# SmartThermo1_6.net
KiCad netlist of a schematic drawn in EAGLE
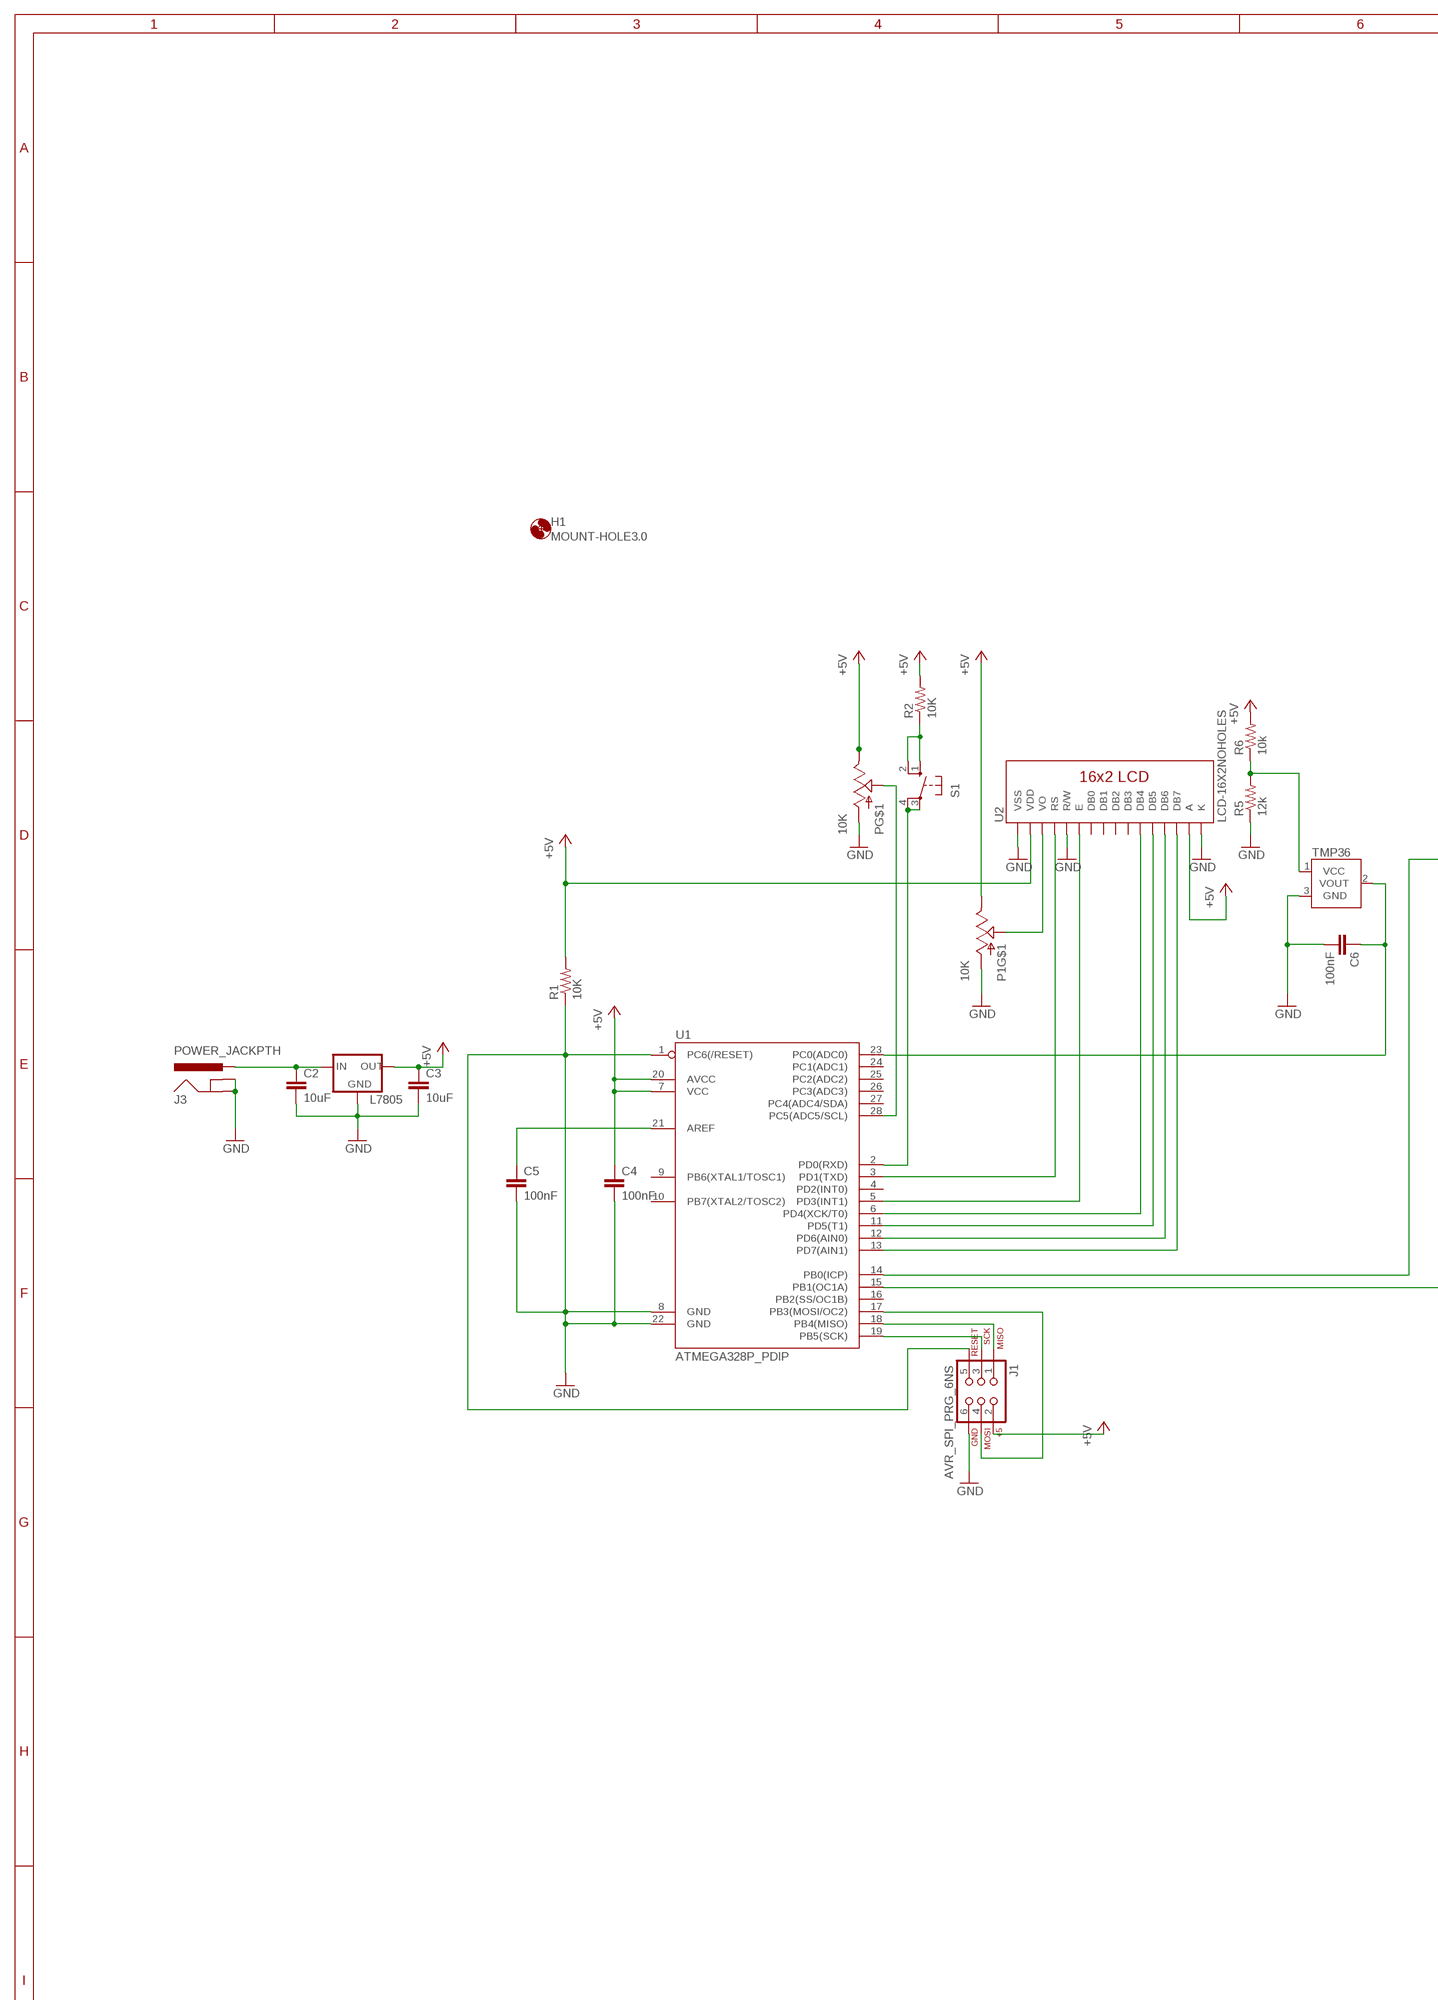
[diagram p0: schematic, sheet 1, part 1 of 2]
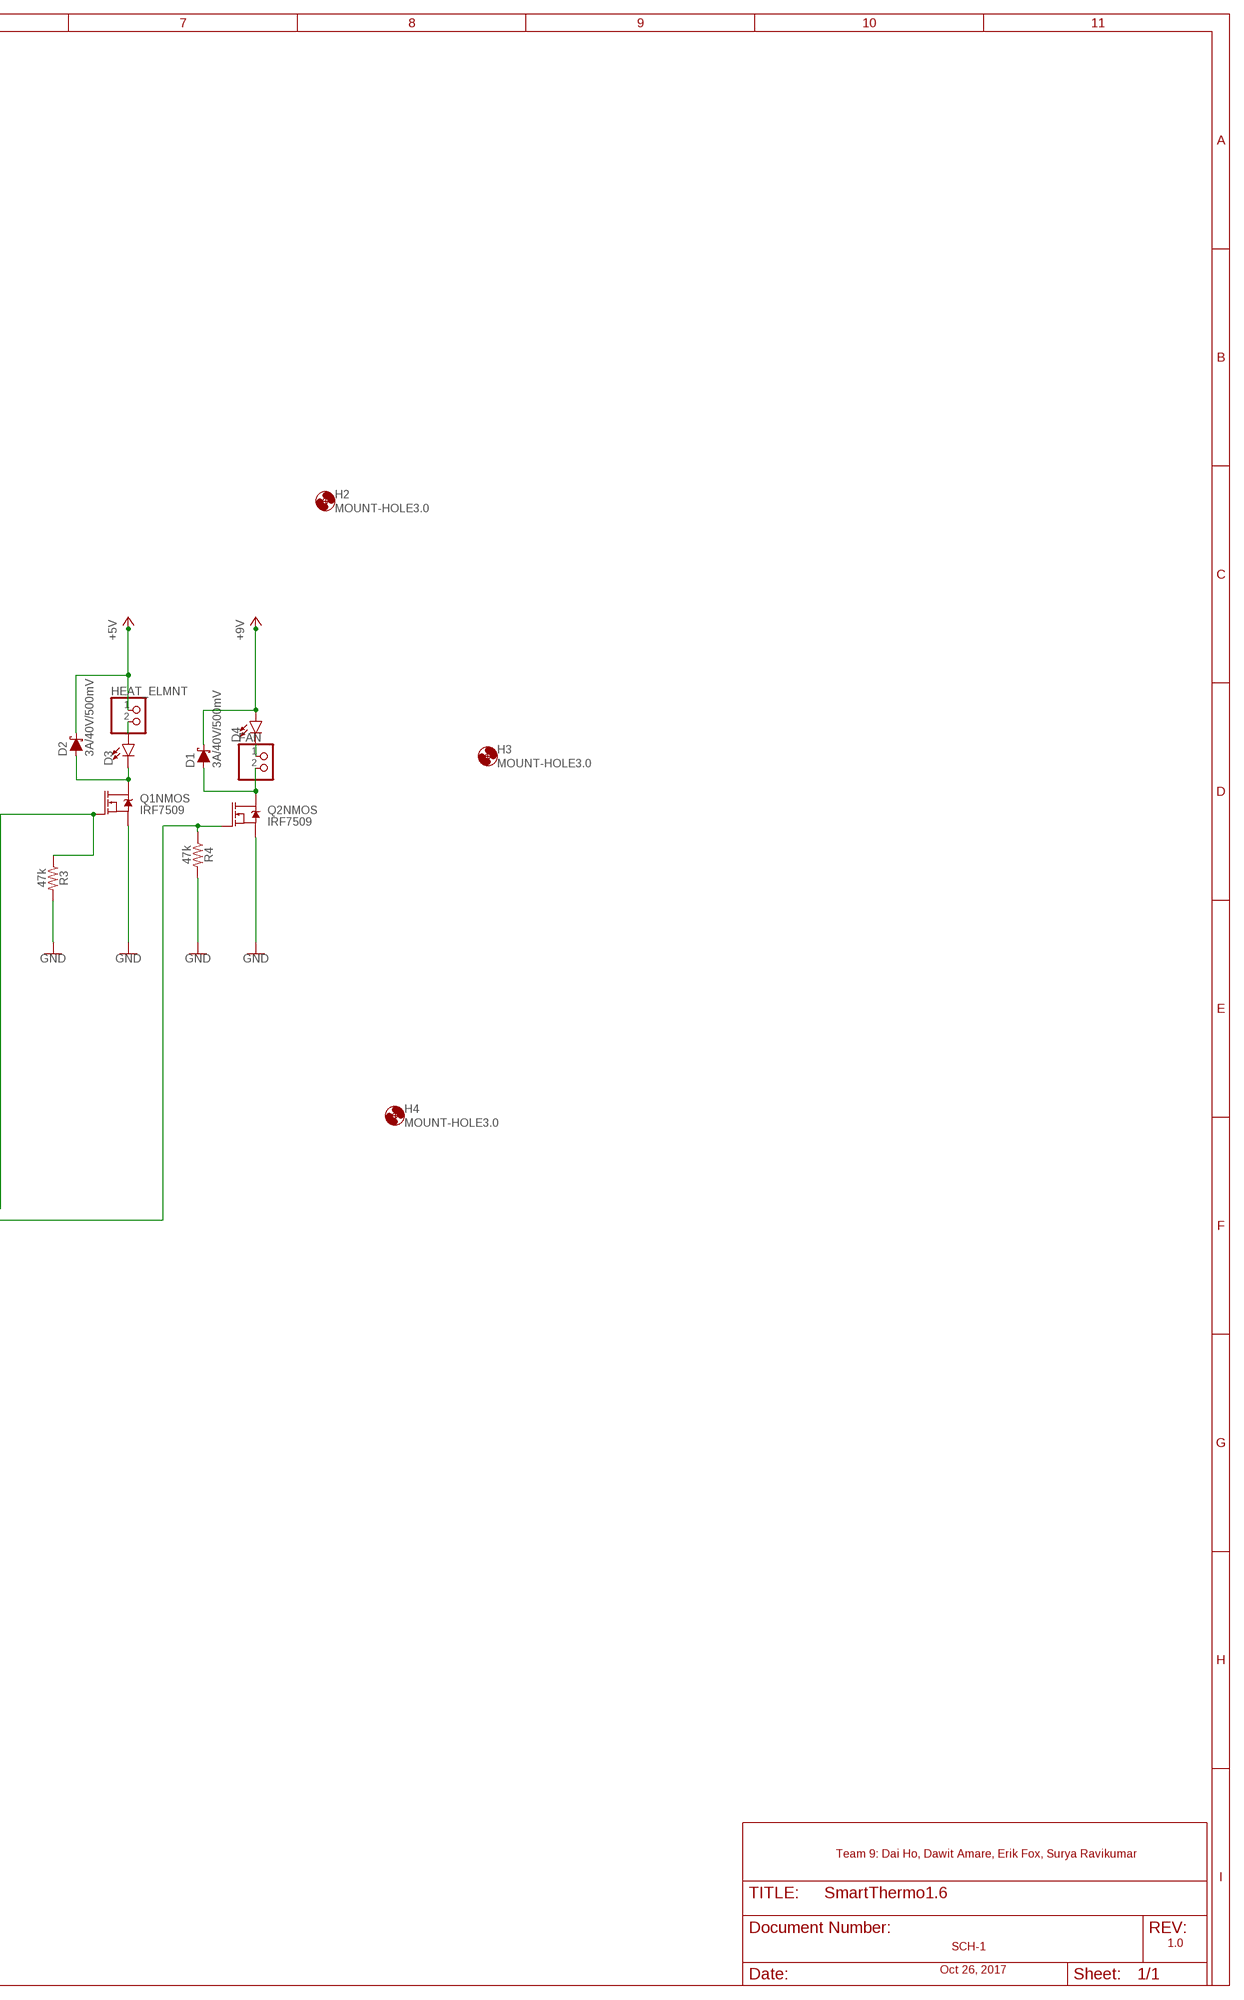
[diagram p1: schematic, sheet 1, part 2 of 2]

(export (version "E")
  (design (tool "Eeschema 10.0.6"))
  (components
    (comp (ref "C2")
      (value "10uF")
      (footprint "eagle-import:C7.5B3")
      (libsource (lib "eagle-import") (part "C7.5/3"))
    )
    (comp (ref "C3")
      (value "10uF")
      (footprint "eagle-import:C7.5B3")
      (libsource (lib "eagle-import") (part "C7.5/3"))
    )
    (comp (ref "C4")
      (value "100nF")
      (footprint "eagle-import:C2.5-2")
      (libsource (lib "eagle-import") (part "C2.5/2"))
    )
    (comp (ref "C5")
      (value "100nF")
      (footprint "eagle-import:C2.5-2")
      (libsource (lib "eagle-import") (part "C2.5/2"))
    )
    (comp (ref "C6")
      (value "100nF")
      (footprint "eagle-import:C2.5-2")
      (libsource (lib "eagle-import") (part "C2.5/2"))
    )
    (comp (ref "D1")
      (value "3A/40V/500mV")
      (footprint "eagle-import:SMA-DIODE")
      (libsource (lib "eagle-import") (part "DIODE-SCHOTTKY-B340A"))
    )
    (comp (ref "D2")
      (value "3A/40V/500mV")
      (footprint "eagle-import:SMA-DIODE")
      (libsource (lib "eagle-import") (part "DIODE-SCHOTTKY-B340A"))
    )
    (comp (ref "D3")
      (value "LED3MM")
      (footprint "eagle-import:LED_3MM")
      (libsource (lib "eagle-import") (part "LED3MM"))
    )
    (comp (ref "D4")
      (value "LED3MM")
      (footprint "eagle-import:LED_3MM")
      (libsource (lib "eagle-import") (part "LED3MM"))
    )
    (comp (ref "FAN")
      (value "PINHD-1X2/90")
      (footprint "eagle-import:1X02_90")
      (libsource (lib "eagle-import") (part "PINHD-1X2/90"))
    )
    (comp (ref "H1")
      (value "MOUNT-HOLE3.0")
      (footprint "eagle-import:3,0")
      (libsource (lib "eagle-import") (part "MOUNT-HOLE3.0"))
    )
    (comp (ref "H2")
      (value "MOUNT-HOLE3.0")
      (footprint "eagle-import:3,0")
      (libsource (lib "eagle-import") (part "MOUNT-HOLE3.0"))
    )
    (comp (ref "H3")
      (value "MOUNT-HOLE3.0")
      (footprint "eagle-import:3,0")
      (libsource (lib "eagle-import") (part "MOUNT-HOLE3.0"))
    )
    (comp (ref "H4")
      (value "MOUNT-HOLE3.0")
      (footprint "eagle-import:3,0")
      (libsource (lib "eagle-import") (part "MOUNT-HOLE3.0"))
    )
    (comp (ref "HEAT_ELMNT")
      (value "PINHD-1X2/90")
      (footprint "eagle-import:1X02_90")
      (libsource (lib "eagle-import") (part "PINHD-1X2/90"))
    )
    (comp (ref "J1")
      (value "AVR_SPI_PRG_6NS")
      (footprint "eagle-import:2X3-NS")
      (libsource (lib "eagle-import") (part "AVR_SPI_PRG_6NS"))
    )
    (comp (ref "J3")
      (value "POWER_JACKPTH")
      (footprint "eagle-import:POWER_JACK_PTH")
      (libsource (lib "eagle-import") (part "POWER_JACKPTH"))
    )
    (comp (ref "L7805")
      (value "78XXL")
      (footprint "eagle-import:78XXL")
      (libsource (lib "eagle-import") (part "78XXL"))
    )
    (comp (ref "P")
      (value "10K")
      (footprint "eagle-import:POT_PTH")
      (libsource (lib "eagle-import") (part "POT_SWITCHPOT_PTH"))
    )
    (comp (ref "P1")
      (value "10K")
      (footprint "eagle-import:POT_PTH")
      (libsource (lib "eagle-import") (part "POT_SWITCHPOT_PTH"))
    )
    (comp (ref "Q1")
      (value "IRF7509")
      (footprint "eagle-import:MSOP8")
      (libsource (lib "eagle-import") (part "IRF7509"))
    )
    (comp (ref "Q2")
      (value "IRF7509")
      (footprint "eagle-import:MSOP8")
      (libsource (lib "eagle-import") (part "IRF7509"))
    )
    (comp (ref "R1")
      (value "10K")
      (footprint "eagle-import:1206")
      (libsource (lib "eagle-import") (part "RESISTOR1206"))
    )
    (comp (ref "R2")
      (value "10K")
      (footprint "eagle-import:1206")
      (libsource (lib "eagle-import") (part "RESISTOR1206"))
    )
    (comp (ref "R3")
      (value "47k")
      (footprint "eagle-import:0603")
      (libsource (lib "eagle-import") (part "47KOHM-0603-1/10W-1%"))
    )
    (comp (ref "R4")
      (value "47k")
      (footprint "eagle-import:0603")
      (libsource (lib "eagle-import") (part "47KOHM-0603-1/10W-1%"))
    )
    (comp (ref "R5")
      (value "12k")
      (footprint "eagle-import:0204_5")
      (libsource (lib "eagle-import") (part "R-US_0204/5"))
    )
    (comp (ref "R6")
      (value "10k")
      (footprint "eagle-import:0204_5")
      (libsource (lib "eagle-import") (part "R-US_0204/5"))
    )
    (comp (ref "S1")
      (value "10-XX")
      (footprint "eagle-import:B3F-10XX")
      (fields (field (name "MPN") "B3F-1000"))
      (libsource (lib "eagle-import") (part "10-XX"))
    )
    (comp (ref "TMP36")
      (value "TMP36GT9")
      (footprint "eagle-import:TO-92")
      (libsource (lib "eagle-import") (part "TMP36GT9"))
    )
    (comp (ref "U1")
      (value "ATMEGA328P_PDIP")
      (footprint "eagle-import:DIL28-3")
      (libsource (lib "eagle-import") (part "ATMEGA328P_PDIP"))
    )
    (comp (ref "U2")
      (value "LCD-16X2NOHOLES")
      (footprint "eagle-import:LCD-16X2_NOHOLES")
      (libsource (lib "eagle-import") (part "LCD-16X2NOHOLES"))
    )
  )
  (nets
    (net (code "1") (name "+5V") (class "Default")
      (node (ref "C3") (pin "1") (pinfunction "1_1") (pintype "passive"))
      (node (ref "C4") (pin "1") (pinfunction "1_1") (pintype "passive"))
      (node (ref "D1") (pin "C") (pinfunction "C_C") (pintype "passive"))
      (node (ref "D2") (pin "C") (pinfunction "C_C") (pintype "passive"))
      (node (ref "D4") (pin "A") (pinfunction "A_A") (pintype "passive"))
      (node (ref "HEAT_ELMNT") (pin "1") (pinfunction "1_1") (pintype "passive"))
      (node (ref "J1") (pin "2") (pinfunction "2_2") (pintype "passive"))
      (node (ref "L7805") (pin "OUT") (pinfunction "OUT_OUT") (pintype "passive"))
      (node (ref "P") (pin "E@2") (pinfunction "E_E@2") (pintype "passive"))
      (node (ref "P1") (pin "E@2") (pinfunction "E_E@2") (pintype "passive"))
      (node (ref "R1") (pin "2") (pinfunction "2_2") (pintype "passive"))
      (node (ref "R2") (pin "2") (pinfunction "2_2") (pintype "passive"))
      (node (ref "R6") (pin "2") (pinfunction "2_2") (pintype "passive"))
      (node (ref "U1") (pin "20") (pinfunction "AVCC_20") (pintype "bidirectional"))
      (node (ref "U1") (pin "7") (pinfunction "VCC_7") (pintype "bidirectional"))
      (node (ref "U2") (pin "15") (pinfunction "A_15") (pintype "power_in"))
      (node (ref "U2") (pin "2") (pinfunction "VDD_2") (pintype "power_in"))
    )
    (net (code "2") (name "GND") (class "Default")
      (node (ref "C2") (pin "2") (pinfunction "2_2") (pintype "passive"))
      (node (ref "C3") (pin "2") (pinfunction "2_2") (pintype "passive"))
      (node (ref "C4") (pin "2") (pinfunction "2_2") (pintype "passive"))
      (node (ref "C5") (pin "2") (pinfunction "2_2") (pintype "passive"))
      (node (ref "C6") (pin "2") (pinfunction "2_2") (pintype "passive"))
      (node (ref "J1") (pin "5") (pinfunction "5_5") (pintype "passive"))
      (node (ref "J1") (pin "6") (pinfunction "6_6") (pintype "passive"))
      (node (ref "J3") (pin "GND") (pinfunction "GND_GND") (pintype "bidirectional"))
      (node (ref "J3") (pin "GNDBREAK") (pinfunction "GNDBREAK_GNDBREAK") (pintype "bidirectional"))
      (node (ref "L7805") (pin "GND") (pinfunction "GND_GND") (pintype "input"))
      (node (ref "P") (pin "E@1") (pinfunction "A_E@1") (pintype "passive"))
      (node (ref "P1") (pin "E@1") (pinfunction "A_E@1") (pintype "passive"))
      (node (ref "Q1") (pin "1") (pinfunction "S_1") (pintype "bidirectional"))
      (node (ref "Q2") (pin "1") (pinfunction "S_1") (pintype "bidirectional"))
      (node (ref "R1") (pin "1") (pinfunction "1_1") (pintype "passive"))
      (node (ref "R3") (pin "2") (pinfunction "2_2") (pintype "passive"))
      (node (ref "R4") (pin "2") (pinfunction "2_2") (pintype "passive"))
      (node (ref "R5") (pin "1") (pinfunction "1_1") (pintype "passive"))
      (node (ref "TMP36") (pin "3") (pinfunction "GND_3") (pintype "bidirectional"))
      (node (ref "U1") (pin "1") (pinfunction "PC6(/RESET)_1") (pintype "bidirectional"))
      (node (ref "U1") (pin "22") (pinfunction "GND_22") (pintype "bidirectional"))
      (node (ref "U1") (pin "8") (pinfunction "GND_8") (pintype "bidirectional"))
      (node (ref "U2") (pin "1") (pinfunction "VSS_1") (pintype "power_in"))
      (node (ref "U2") (pin "16") (pinfunction "K_16") (pintype "power_in"))
      (node (ref "U2") (pin "5") (pinfunction "R/W_5") (pintype "input"))
    )
    (net (code "3") (name "Net-(C2-Pad1)") (class "Default")
      (node (ref "C2") (pin "1") (pinfunction "1_1") (pintype "passive"))
      (node (ref "J3") (pin "PWR") (pinfunction "PWR_PWR") (pintype "bidirectional"))
      (node (ref "L7805") (pin "IN") (pinfunction "IN_IN") (pintype "input"))
    )
    (net (code "4") (name "Net-(D1-PadA)") (class "Default")
      (node (ref "D1") (pin "A") (pinfunction "A_A") (pintype "passive"))
      (node (ref "FAN") (pin "2") (pinfunction "2_2") (pintype "passive"))
      (node (ref "Q2") (pin "7") (pinfunction "D_7") (pintype "bidirectional"))
      (node (ref "Q2") (pin "8") (pinfunction "D_8") (pintype "bidirectional"))
    )
    (net (code "5") (name "Net-(D3-C)") (class "Default")
      (node (ref "D2") (pin "A") (pinfunction "A_A") (pintype "passive"))
      (node (ref "D3") (pin "K") (pinfunction "C_K") (pintype "passive"))
      (node (ref "Q1") (pin "7") (pinfunction "D_7") (pintype "bidirectional"))
      (node (ref "Q1") (pin "8") (pinfunction "D_8") (pintype "bidirectional"))
    )
    (net (code "6") (name "Net-(D3-PadA)") (class "Default")
      (node (ref "D3") (pin "A") (pinfunction "A_A") (pintype "passive"))
      (node (ref "HEAT_ELMNT") (pin "2") (pinfunction "2_2") (pintype "passive"))
    )
    (net (code "7") (name "Net-(D4-C)") (class "Default")
      (node (ref "D4") (pin "K") (pinfunction "C_K") (pintype "passive"))
      (node (ref "FAN") (pin "1") (pinfunction "1_1") (pintype "passive"))
    )
    (net (code "8") (name "Net-(P1A-S)") (class "Default")
      (node (ref "P1") (pin "WAND") (pinfunction "S_WAND") (pintype "passive"))
      (node (ref "U2") (pin "3") (pinfunction "VO_3") (pintype "bidirectional"))
    )
    (net (code "9") (name "Net-(PA-S)") (class "Default")
      (node (ref "P") (pin "WAND") (pinfunction "S_WAND") (pintype "passive"))
      (node (ref "U1") (pin "28") (pinfunction "PC5(ADC5/SCL)_28") (pintype "bidirectional"))
    )
    (net (code "10") (name "Net-(Q1A-G)") (class "Default")
      (node (ref "Q1") (pin "2") (pinfunction "G_2") (pintype "bidirectional"))
      (node (ref "R3") (pin "1") (pinfunction "1_1") (pintype "passive"))
      (node (ref "U1") (pin "14") (pinfunction "PB0(ICP)_14") (pintype "bidirectional"))
    )
    (net (code "11") (name "Net-(Q2A-G)") (class "Default")
      (node (ref "Q2") (pin "2") (pinfunction "G_2") (pintype "bidirectional"))
      (node (ref "R4") (pin "1") (pinfunction "1_1") (pintype "passive"))
      (node (ref "U1") (pin "15") (pinfunction "PB1(OC1A)_15") (pintype "bidirectional"))
    )
    (net (code "12") (name "Net-(S1-P)") (class "Default")
      (node (ref "S1") (pin "3") (pinfunction "P_3") (pintype "passive"))
      (node (ref "S1") (pin "4") (pinfunction "P1_4") (pintype "passive"))
      (node (ref "U1") (pin "2") (pinfunction "PD0(RXD)_2") (pintype "bidirectional"))
    )
    (net (code "13") (name "Net-(S1-S)") (class "Default")
      (node (ref "R2") (pin "1") (pinfunction "1_1") (pintype "passive"))
      (node (ref "S1") (pin "1") (pinfunction "S_1") (pintype "passive"))
      (node (ref "S1") (pin "2") (pinfunction "S1_2") (pintype "passive"))
    )
    (net (code "14") (name "Net-(TMP36-VCC)") (class "Default")
      (node (ref "R5") (pin "2") (pinfunction "2_2") (pintype "passive"))
      (node (ref "R6") (pin "1") (pinfunction "1_1") (pintype "passive"))
      (node (ref "TMP36") (pin "1") (pinfunction "VCC_1") (pintype "bidirectional"))
    )
    (net (code "15") (name "Net-(TMP36-VOUT)") (class "Default")
      (node (ref "C6") (pin "1") (pinfunction "1_1") (pintype "passive"))
      (node (ref "TMP36") (pin "2") (pinfunction "VOUT_2") (pintype "bidirectional"))
      (node (ref "U1") (pin "23") (pinfunction "PC0(ADC0)_23") (pintype "bidirectional"))
    )
    (net (code "16") (name "Net-(U1-AREF)") (class "Default")
      (node (ref "C5") (pin "1") (pinfunction "1_1") (pintype "passive"))
      (node (ref "U1") (pin "21") (pinfunction "AREF_21") (pintype "bidirectional"))
    )
    (net (code "17") (name "Net-(U1-PB3(MOSI{slash}OC2))") (class "Default")
      (node (ref "J1") (pin "4") (pinfunction "4_4") (pintype "passive"))
      (node (ref "U1") (pin "17") (pinfunction "PB3(MOSI/OC2)_17") (pintype "bidirectional"))
    )
    (net (code "18") (name "Net-(U1-PB4(MISO))") (class "Default")
      (node (ref "J1") (pin "1") (pinfunction "1_1") (pintype "passive"))
      (node (ref "U1") (pin "18") (pinfunction "PB4(MISO)_18") (pintype "bidirectional"))
    )
    (net (code "19") (name "Net-(U1-PB5(SCK))") (class "Default")
      (node (ref "J1") (pin "3") (pinfunction "3_3") (pintype "passive"))
      (node (ref "U1") (pin "19") (pinfunction "PB5(SCK)_19") (pintype "bidirectional"))
    )
    (net (code "20") (name "Net-(U1-PD1(TXD))") (class "Default")
      (node (ref "U1") (pin "3") (pinfunction "PD1(TXD)_3") (pintype "bidirectional"))
      (node (ref "U2") (pin "4") (pinfunction "RS_4") (pintype "input"))
    )
    (net (code "21") (name "Net-(U1-PD3(INT1))") (class "Default")
      (node (ref "U1") (pin "5") (pinfunction "PD3(INT1)_5") (pintype "bidirectional"))
      (node (ref "U2") (pin "6") (pinfunction "E_6") (pintype "input"))
    )
    (net (code "22") (name "Net-(U1-PD4(XCK{slash}T0))") (class "Default")
      (node (ref "U1") (pin "6") (pinfunction "PD4(XCK/T0)_6") (pintype "bidirectional"))
      (node (ref "U2") (pin "11") (pinfunction "DB4_11") (pintype "bidirectional"))
    )
    (net (code "23") (name "Net-(U1-PD5(T1))") (class "Default")
      (node (ref "U1") (pin "11") (pinfunction "PD5(T1)_11") (pintype "bidirectional"))
      (node (ref "U2") (pin "12") (pinfunction "DB5_12") (pintype "bidirectional"))
    )
    (net (code "24") (name "Net-(U1-PD6(AIN0))") (class "Default")
      (node (ref "U1") (pin "12") (pinfunction "PD6(AIN0)_12") (pintype "bidirectional"))
      (node (ref "U2") (pin "13") (pinfunction "DB6_13") (pintype "bidirectional"))
    )
    (net (code "25") (name "Net-(U1-PD7(AIN1))") (class "Default")
      (node (ref "U1") (pin "13") (pinfunction "PD7(AIN1)_13") (pintype "bidirectional"))
      (node (ref "U2") (pin "14") (pinfunction "DB7_14") (pintype "bidirectional"))
    )
    (net (code "26") (name "unconnected-(U1-PB2(SS{slash}OC1B)-Pad16)") (class "Default")
      (node (ref "U1") (pin "16") (pinfunction "PB2(SS/OC1B)_16") (pintype "bidirectional"))
    )
    (net (code "27") (name "unconnected-(U1-PB6(XTAL1{slash}TOSC1)-Pad9)") (class "Default")
      (node (ref "U1") (pin "9") (pinfunction "PB6(XTAL1/TOSC1)_9") (pintype "bidirectional"))
    )
    (net (code "28") (name "unconnected-(U1-PB7(XTAL2{slash}TOSC2)-Pad10)") (class "Default")
      (node (ref "U1") (pin "10") (pinfunction "PB7(XTAL2/TOSC2)_10") (pintype "bidirectional"))
    )
    (net (code "29") (name "unconnected-(U1-PC1(ADC1)-Pad24)") (class "Default")
      (node (ref "U1") (pin "24") (pinfunction "PC1(ADC1)_24") (pintype "bidirectional"))
    )
    (net (code "30") (name "unconnected-(U1-PC2(ADC2)-Pad25)") (class "Default")
      (node (ref "U1") (pin "25") (pinfunction "PC2(ADC2)_25") (pintype "bidirectional"))
    )
    (net (code "31") (name "unconnected-(U1-PC3(ADC3)-Pad26)") (class "Default")
      (node (ref "U1") (pin "26") (pinfunction "PC3(ADC3)_26") (pintype "bidirectional"))
    )
    (net (code "32") (name "unconnected-(U1-PC4(ADC4{slash}SDA)-Pad27)") (class "Default")
      (node (ref "U1") (pin "27") (pinfunction "PC4(ADC4/SDA)_27") (pintype "bidirectional"))
    )
    (net (code "33") (name "unconnected-(U1-PD2(INT0)-Pad4)") (class "Default")
      (node (ref "U1") (pin "4") (pinfunction "PD2(INT0)_4") (pintype "bidirectional"))
    )
    (net (code "34") (name "unconnected-(U2-DB0-Pad7)") (class "Default")
      (node (ref "U2") (pin "7") (pinfunction "DB0_7") (pintype "bidirectional"))
    )
    (net (code "35") (name "unconnected-(U2-DB1-Pad8)") (class "Default")
      (node (ref "U2") (pin "8") (pinfunction "DB1_8") (pintype "bidirectional"))
    )
    (net (code "36") (name "unconnected-(U2-DB2-Pad9)") (class "Default")
      (node (ref "U2") (pin "9") (pinfunction "DB2_9") (pintype "bidirectional"))
    )
    (net (code "37") (name "unconnected-(U2-DB3-Pad10)") (class "Default")
      (node (ref "U2") (pin "10") (pinfunction "DB3_10") (pintype "bidirectional"))
    )
  )
)
